# Status_LEDs.net
KiCad netlist of a schematic drawn in Altium Designer
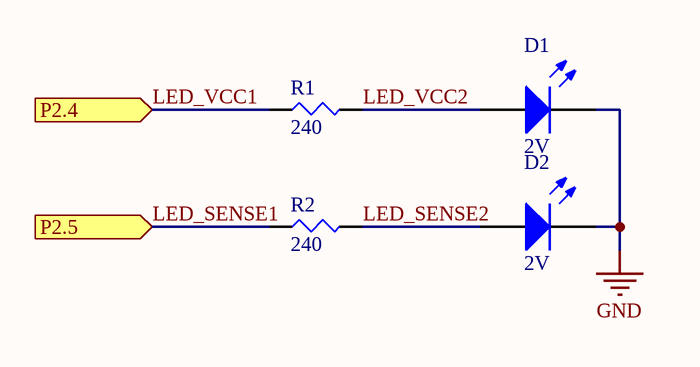
[diagram p0: Status LEDs.SchDoc]

(export (version "E")
  (design (tool "Eeschema 10.0.6"))
  (components
    (comp (ref "D1")
      (value "2V")
      (footprint "0805_A")
      (description "SMD mono-color Chip LED, WL-SMCW, Bright Green, 150080VS75000")
      (fields (field (name "PARTNUMBER") "150080VS75000") (field (name "MANUFACTURER") "Wuerth Elektronik"))
      (libsource (lib "Altium Content Vault") (part "WE-LED_K1A2-2"))
    )
    (comp (ref "D2")
      (value "2V")
      (footprint "0805_A")
      (description "SMD mono-color Chip LED, WL-SMCW, Bright Green, 150080VS75000")
      (fields (field (name "PARTNUMBER") "150080VS75000") (field (name "MANUFACTURER") "Wuerth Elektronik"))
      (libsource (lib "Altium Content Vault") (part "WE-LED_K1A2-2"))
    )
    (comp (ref "R1")
      (value "240")
      (footprint "SMD-0805-RES")
      (description "RES SMD 240 OHM 5% 1/8W 0805")
      (fields (field (name "PART NUMBER") "ERJ-6GEYJ241V") (field (name "DIGI-KEY PART NUMBER") "P240ACT-ND"))
      (libsource (lib "Panasonic_resistor_0805") (part "ERJ-6GEYJ241V"))
    )
    (comp (ref "R2")
      (value "240")
      (footprint "SMD-0805-RES")
      (description "RES SMD 240 OHM 5% 1/8W 0805")
      (fields (field (name "PART NUMBER") "ERJ-6GEYJ241V") (field (name "DIGI-KEY PART NUMBER") "P240ACT-ND"))
      (libsource (lib "Panasonic_resistor_0805") (part "ERJ-6GEYJ241V"))
    )
  )
  (nets
    (net (code "1") (name "/LED_SENSE1") (class "Default")
      (node (ref "R2") (pin "1") (pinfunction "1_1") (pintype "passive"))
    )
    (net (code "2") (name "/LED_SENSE2") (class "Default")
      (node (ref "D2") (pin "2") (pinfunction "A_2") (pintype "passive"))
      (node (ref "R2") (pin "2") (pinfunction "2_2") (pintype "passive"))
    )
    (net (code "3") (name "/LED_VCC1") (class "Default")
      (node (ref "R1") (pin "1") (pinfunction "1_1") (pintype "passive"))
    )
    (net (code "4") (name "/LED_VCC2") (class "Default")
      (node (ref "D1") (pin "2") (pinfunction "A_2") (pintype "passive"))
      (node (ref "R1") (pin "2") (pinfunction "2_2") (pintype "passive"))
    )
    (net (code "5") (name "GND") (class "Default")
      (node (ref "D1") (pin "1") (pinfunction "K_1") (pintype "passive"))
      (node (ref "D2") (pin "1") (pinfunction "K_1") (pintype "passive"))
    )
  )
)
